# 8x8LED_Matrix_v1_0.net
KiCad netlist of a schematic drawn in EAGLE
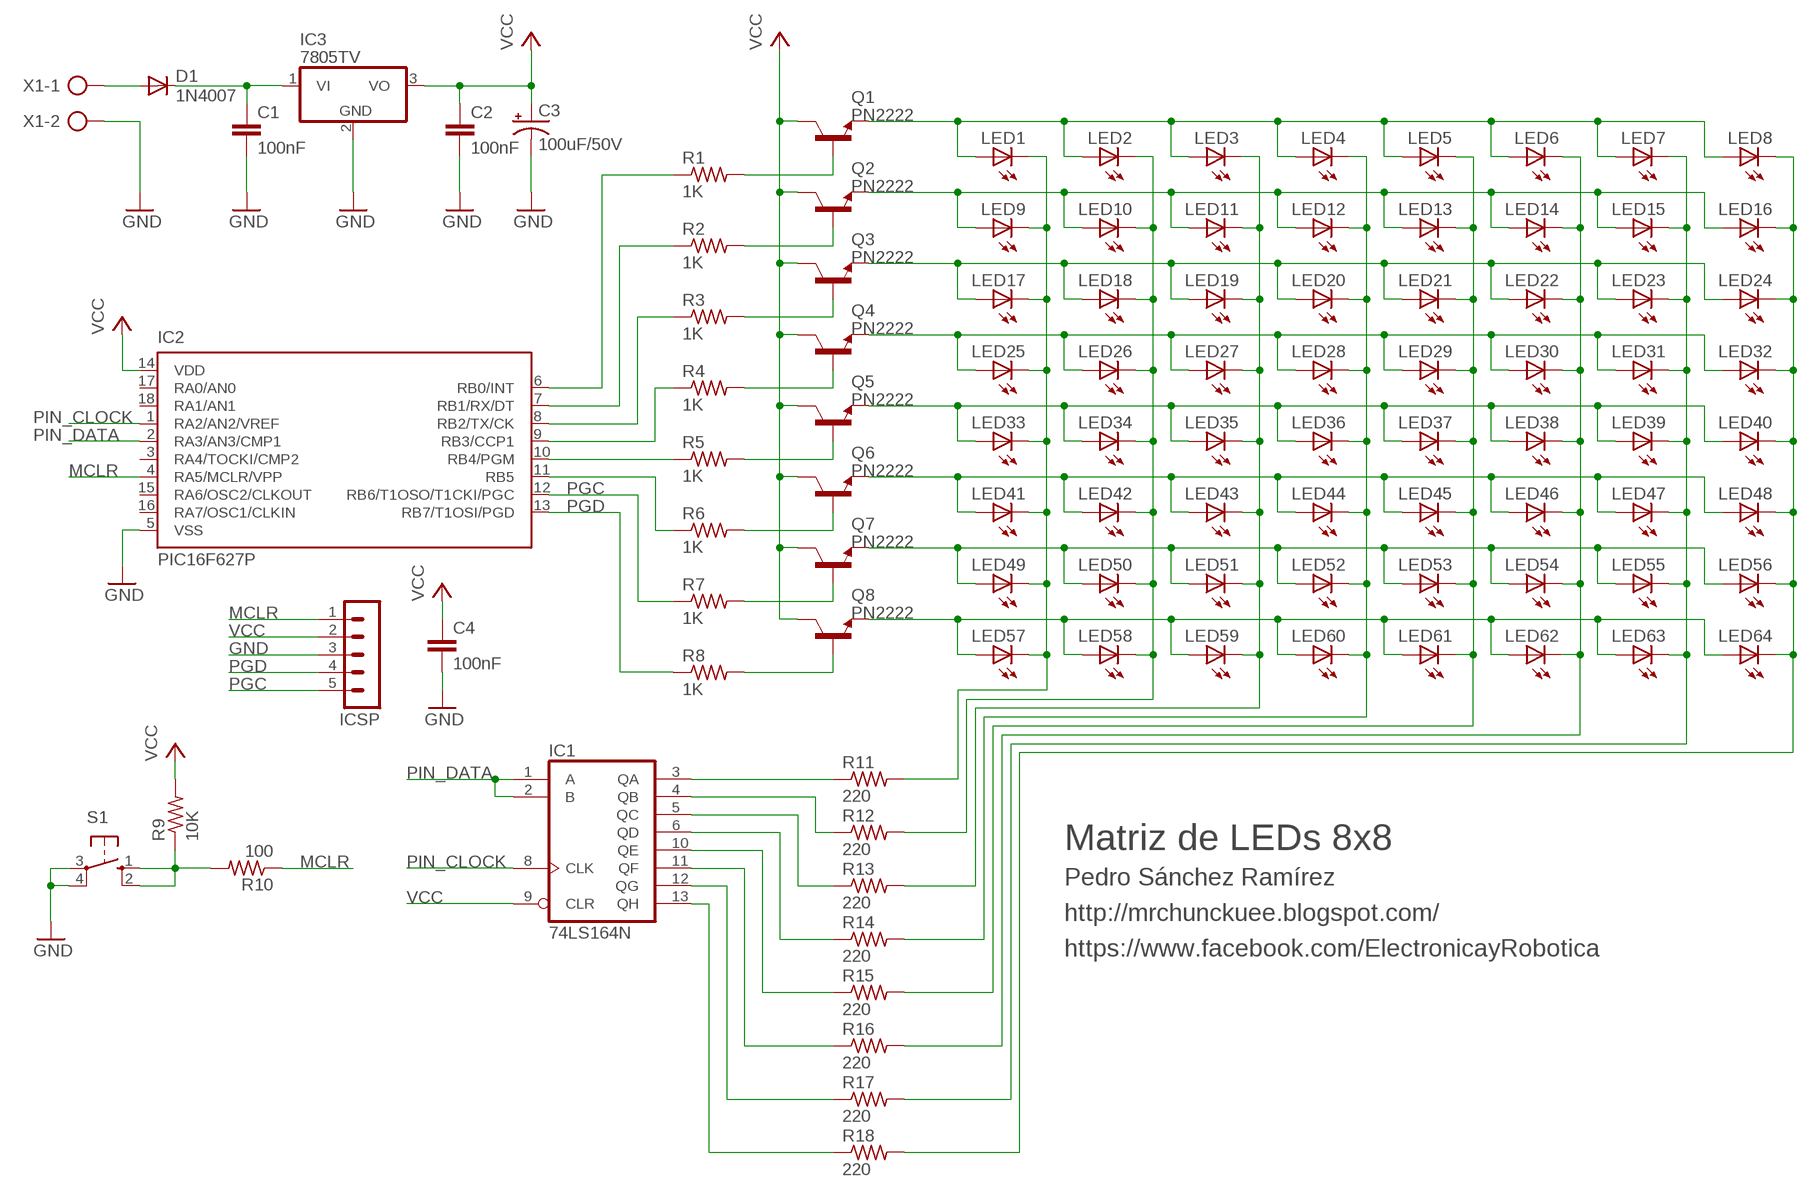
[diagram p0: schematic, sheet 1]

(export (version "E")
  (design (tool "Eeschema 10.0.6"))
  (components
    (comp (ref "C1")
      (value "100nF")
      (footprint "eagle-import:C050-024X044")
      (libsource (lib "eagle-import") (part "C-EU050-024X044"))
    )
    (comp (ref "C2")
      (value "100nF")
      (footprint "eagle-import:C050-024X044")
      (libsource (lib "eagle-import") (part "C-EU050-024X044"))
    )
    (comp (ref "C3")
      (value "100uF/50V")
      (footprint "eagle-import:E5-10,5")
      (libsource (lib "eagle-import") (part "CPOL-USE5-10.5"))
    )
    (comp (ref "C4")
      (value "100nF")
      (footprint "eagle-import:C050-024X044")
      (libsource (lib "eagle-import") (part "C-EU050-024X044"))
    )
    (comp (ref "D1")
      (value "1N4007")
      (footprint "eagle-import:DO41-10")
      (libsource (lib "eagle-import") (part "1N4004"))
    )
    (comp (ref "IC1")
      (value "74LS164N")
      (footprint "eagle-import:DIL14")
      (libsource (lib "eagle-import") (part "74164NLS"))
    )
    (comp (ref "IC2")
      (value "PIC16F627P")
      (footprint "eagle-import:DIL18")
      (fields (field (name "MF") "MICROCHIP") (field (name "MPN") "PIC16F627-04/P"))
      (libsource (lib "eagle-import") (part "PIC16F62P7"))
    )
    (comp (ref "IC3")
      (value "7805TV")
      (footprint "eagle-import:TO220V")
      (libsource (lib "eagle-import") (part "78TV05"))
    )
    (comp (ref "ICSP")
      (value "MA05-1")
      (footprint "eagle-import:MA05-1")
      (libsource (lib "eagle-import") (part "MA05-1"))
    )
    (comp (ref "LED1")
      (value "LED5MM")
      (footprint "eagle-import:LED5MM")
      (libsource (lib "eagle-import") (part "LED5MM"))
    )
    (comp (ref "LED2")
      (value "LED5MM")
      (footprint "eagle-import:LED5MM")
      (libsource (lib "eagle-import") (part "LED5MM"))
    )
    (comp (ref "LED3")
      (value "LED5MM")
      (footprint "eagle-import:LED5MM")
      (libsource (lib "eagle-import") (part "LED5MM"))
    )
    (comp (ref "LED4")
      (value "LED5MM")
      (footprint "eagle-import:LED5MM")
      (libsource (lib "eagle-import") (part "LED5MM"))
    )
    (comp (ref "LED5")
      (value "LED5MM")
      (footprint "eagle-import:LED5MM")
      (libsource (lib "eagle-import") (part "LED5MM"))
    )
    (comp (ref "LED6")
      (value "LED5MM")
      (footprint "eagle-import:LED5MM")
      (libsource (lib "eagle-import") (part "LED5MM"))
    )
    (comp (ref "LED7")
      (value "LED5MM")
      (footprint "eagle-import:LED5MM")
      (libsource (lib "eagle-import") (part "LED5MM"))
    )
    (comp (ref "LED8")
      (value "LED5MM")
      (footprint "eagle-import:LED5MM")
      (libsource (lib "eagle-import") (part "LED5MM"))
    )
    (comp (ref "LED9")
      (value "LED5MM")
      (footprint "eagle-import:LED5MM")
      (libsource (lib "eagle-import") (part "LED5MM"))
    )
    (comp (ref "LED10")
      (value "LED5MM")
      (footprint "eagle-import:LED5MM")
      (libsource (lib "eagle-import") (part "LED5MM"))
    )
    (comp (ref "LED11")
      (value "LED5MM")
      (footprint "eagle-import:LED5MM")
      (libsource (lib "eagle-import") (part "LED5MM"))
    )
    (comp (ref "LED12")
      (value "LED5MM")
      (footprint "eagle-import:LED5MM")
      (libsource (lib "eagle-import") (part "LED5MM"))
    )
    (comp (ref "LED13")
      (value "LED5MM")
      (footprint "eagle-import:LED5MM")
      (libsource (lib "eagle-import") (part "LED5MM"))
    )
    (comp (ref "LED14")
      (value "LED5MM")
      (footprint "eagle-import:LED5MM")
      (libsource (lib "eagle-import") (part "LED5MM"))
    )
    (comp (ref "LED15")
      (value "LED5MM")
      (footprint "eagle-import:LED5MM")
      (libsource (lib "eagle-import") (part "LED5MM"))
    )
    (comp (ref "LED16")
      (value "LED5MM")
      (footprint "eagle-import:LED5MM")
      (libsource (lib "eagle-import") (part "LED5MM"))
    )
    (comp (ref "LED17")
      (value "LED5MM")
      (footprint "eagle-import:LED5MM")
      (libsource (lib "eagle-import") (part "LED5MM"))
    )
    (comp (ref "LED18")
      (value "LED5MM")
      (footprint "eagle-import:LED5MM")
      (libsource (lib "eagle-import") (part "LED5MM"))
    )
    (comp (ref "LED19")
      (value "LED5MM")
      (footprint "eagle-import:LED5MM")
      (libsource (lib "eagle-import") (part "LED5MM"))
    )
    (comp (ref "LED20")
      (value "LED5MM")
      (footprint "eagle-import:LED5MM")
      (libsource (lib "eagle-import") (part "LED5MM"))
    )
    (comp (ref "LED21")
      (value "LED5MM")
      (footprint "eagle-import:LED5MM")
      (libsource (lib "eagle-import") (part "LED5MM"))
    )
    (comp (ref "LED22")
      (value "LED5MM")
      (footprint "eagle-import:LED5MM")
      (libsource (lib "eagle-import") (part "LED5MM"))
    )
    (comp (ref "LED23")
      (value "LED5MM")
      (footprint "eagle-import:LED5MM")
      (libsource (lib "eagle-import") (part "LED5MM"))
    )
    (comp (ref "LED24")
      (value "LED5MM")
      (footprint "eagle-import:LED5MM")
      (libsource (lib "eagle-import") (part "LED5MM"))
    )
    (comp (ref "LED25")
      (value "LED5MM")
      (footprint "eagle-import:LED5MM")
      (libsource (lib "eagle-import") (part "LED5MM"))
    )
    (comp (ref "LED26")
      (value "LED5MM")
      (footprint "eagle-import:LED5MM")
      (libsource (lib "eagle-import") (part "LED5MM"))
    )
    (comp (ref "LED27")
      (value "LED5MM")
      (footprint "eagle-import:LED5MM")
      (libsource (lib "eagle-import") (part "LED5MM"))
    )
    (comp (ref "LED28")
      (value "LED5MM")
      (footprint "eagle-import:LED5MM")
      (libsource (lib "eagle-import") (part "LED5MM"))
    )
    (comp (ref "LED29")
      (value "LED5MM")
      (footprint "eagle-import:LED5MM")
      (libsource (lib "eagle-import") (part "LED5MM"))
    )
    (comp (ref "LED30")
      (value "LED5MM")
      (footprint "eagle-import:LED5MM")
      (libsource (lib "eagle-import") (part "LED5MM"))
    )
    (comp (ref "LED31")
      (value "LED5MM")
      (footprint "eagle-import:LED5MM")
      (libsource (lib "eagle-import") (part "LED5MM"))
    )
    (comp (ref "LED32")
      (value "LED5MM")
      (footprint "eagle-import:LED5MM")
      (libsource (lib "eagle-import") (part "LED5MM"))
    )
    (comp (ref "LED33")
      (value "LED5MM")
      (footprint "eagle-import:LED5MM")
      (libsource (lib "eagle-import") (part "LED5MM"))
    )
    (comp (ref "LED34")
      (value "LED5MM")
      (footprint "eagle-import:LED5MM")
      (libsource (lib "eagle-import") (part "LED5MM"))
    )
    (comp (ref "LED35")
      (value "LED5MM")
      (footprint "eagle-import:LED5MM")
      (libsource (lib "eagle-import") (part "LED5MM"))
    )
    (comp (ref "LED36")
      (value "LED5MM")
      (footprint "eagle-import:LED5MM")
      (libsource (lib "eagle-import") (part "LED5MM"))
    )
    (comp (ref "LED37")
      (value "LED5MM")
      (footprint "eagle-import:LED5MM")
      (libsource (lib "eagle-import") (part "LED5MM"))
    )
    (comp (ref "LED38")
      (value "LED5MM")
      (footprint "eagle-import:LED5MM")
      (libsource (lib "eagle-import") (part "LED5MM"))
    )
    (comp (ref "LED39")
      (value "LED5MM")
      (footprint "eagle-import:LED5MM")
      (libsource (lib "eagle-import") (part "LED5MM"))
    )
    (comp (ref "LED40")
      (value "LED5MM")
      (footprint "eagle-import:LED5MM")
      (libsource (lib "eagle-import") (part "LED5MM"))
    )
    (comp (ref "LED41")
      (value "LED5MM")
      (footprint "eagle-import:LED5MM")
      (libsource (lib "eagle-import") (part "LED5MM"))
    )
    (comp (ref "LED42")
      (value "LED5MM")
      (footprint "eagle-import:LED5MM")
      (libsource (lib "eagle-import") (part "LED5MM"))
    )
    (comp (ref "LED43")
      (value "LED5MM")
      (footprint "eagle-import:LED5MM")
      (libsource (lib "eagle-import") (part "LED5MM"))
    )
    (comp (ref "LED44")
      (value "LED5MM")
      (footprint "eagle-import:LED5MM")
      (libsource (lib "eagle-import") (part "LED5MM"))
    )
    (comp (ref "LED45")
      (value "LED5MM")
      (footprint "eagle-import:LED5MM")
      (libsource (lib "eagle-import") (part "LED5MM"))
    )
    (comp (ref "LED46")
      (value "LED5MM")
      (footprint "eagle-import:LED5MM")
      (libsource (lib "eagle-import") (part "LED5MM"))
    )
    (comp (ref "LED47")
      (value "LED5MM")
      (footprint "eagle-import:LED5MM")
      (libsource (lib "eagle-import") (part "LED5MM"))
    )
    (comp (ref "LED48")
      (value "LED5MM")
      (footprint "eagle-import:LED5MM")
      (libsource (lib "eagle-import") (part "LED5MM"))
    )
    (comp (ref "LED49")
      (value "LED5MM")
      (footprint "eagle-import:LED5MM")
      (libsource (lib "eagle-import") (part "LED5MM"))
    )
    (comp (ref "LED50")
      (value "LED5MM")
      (footprint "eagle-import:LED5MM")
      (libsource (lib "eagle-import") (part "LED5MM"))
    )
    (comp (ref "LED51")
      (value "LED5MM")
      (footprint "eagle-import:LED5MM")
      (libsource (lib "eagle-import") (part "LED5MM"))
    )
    (comp (ref "LED52")
      (value "LED5MM")
      (footprint "eagle-import:LED5MM")
      (libsource (lib "eagle-import") (part "LED5MM"))
    )
    (comp (ref "LED53")
      (value "LED5MM")
      (footprint "eagle-import:LED5MM")
      (libsource (lib "eagle-import") (part "LED5MM"))
    )
    (comp (ref "LED54")
      (value "LED5MM")
      (footprint "eagle-import:LED5MM")
      (libsource (lib "eagle-import") (part "LED5MM"))
    )
    (comp (ref "LED55")
      (value "LED5MM")
      (footprint "eagle-import:LED5MM")
      (libsource (lib "eagle-import") (part "LED5MM"))
    )
    (comp (ref "LED56")
      (value "LED5MM")
      (footprint "eagle-import:LED5MM")
      (libsource (lib "eagle-import") (part "LED5MM"))
    )
    (comp (ref "LED57")
      (value "LED5MM")
      (footprint "eagle-import:LED5MM")
      (libsource (lib "eagle-import") (part "LED5MM"))
    )
    (comp (ref "LED58")
      (value "LED5MM")
      (footprint "eagle-import:LED5MM")
      (libsource (lib "eagle-import") (part "LED5MM"))
    )
    (comp (ref "LED59")
      (value "LED5MM")
      (footprint "eagle-import:LED5MM")
      (libsource (lib "eagle-import") (part "LED5MM"))
    )
    (comp (ref "LED60")
      (value "LED5MM")
      (footprint "eagle-import:LED5MM")
      (libsource (lib "eagle-import") (part "LED5MM"))
    )
    (comp (ref "LED61")
      (value "LED5MM")
      (footprint "eagle-import:LED5MM")
      (libsource (lib "eagle-import") (part "LED5MM"))
    )
    (comp (ref "LED62")
      (value "LED5MM")
      (footprint "eagle-import:LED5MM")
      (libsource (lib "eagle-import") (part "LED5MM"))
    )
    (comp (ref "LED63")
      (value "LED5MM")
      (footprint "eagle-import:LED5MM")
      (libsource (lib "eagle-import") (part "LED5MM"))
    )
    (comp (ref "LED64")
      (value "LED5MM")
      (footprint "eagle-import:LED5MM")
      (libsource (lib "eagle-import") (part "LED5MM"))
    )
    (comp (ref "Q1")
      (value "PN2222")
      (footprint "eagle-import:TO92-EBC")
      (libsource (lib "eagle-import") (part "-NPN-TO92-EBC2N4124"))
    )
    (comp (ref "Q2")
      (value "PN2222")
      (footprint "eagle-import:TO92-EBC")
      (libsource (lib "eagle-import") (part "-NPN-TO92-EBC2N4124"))
    )
    (comp (ref "Q3")
      (value "PN2222")
      (footprint "eagle-import:TO92-EBC")
      (libsource (lib "eagle-import") (part "-NPN-TO92-EBC2N4124"))
    )
    (comp (ref "Q4")
      (value "PN2222")
      (footprint "eagle-import:TO92-EBC")
      (libsource (lib "eagle-import") (part "-NPN-TO92-EBC2N4124"))
    )
    (comp (ref "Q5")
      (value "PN2222")
      (footprint "eagle-import:TO92-EBC")
      (libsource (lib "eagle-import") (part "-NPN-TO92-EBC2N4124"))
    )
    (comp (ref "Q6")
      (value "PN2222")
      (footprint "eagle-import:TO92-EBC")
      (libsource (lib "eagle-import") (part "-NPN-TO92-EBC2N4124"))
    )
    (comp (ref "Q7")
      (value "PN2222")
      (footprint "eagle-import:TO92-EBC")
      (libsource (lib "eagle-import") (part "-NPN-TO92-EBC2N4124"))
    )
    (comp (ref "Q8")
      (value "PN2222")
      (footprint "eagle-import:TO92-EBC")
      (libsource (lib "eagle-import") (part "-NPN-TO92-EBC2N4124"))
    )
    (comp (ref "R1")
      (value "1K")
      (footprint "eagle-import:0204_7")
      (libsource (lib "eagle-import") (part "R-US_0204/7"))
    )
    (comp (ref "R2")
      (value "1K")
      (footprint "eagle-import:0204_7")
      (libsource (lib "eagle-import") (part "R-US_0204/7"))
    )
    (comp (ref "R3")
      (value "1K")
      (footprint "eagle-import:0204_7")
      (libsource (lib "eagle-import") (part "R-US_0204/7"))
    )
    (comp (ref "R4")
      (value "1K")
      (footprint "eagle-import:0204_7")
      (libsource (lib "eagle-import") (part "R-US_0204/7"))
    )
    (comp (ref "R5")
      (value "1K")
      (footprint "eagle-import:0204_7")
      (libsource (lib "eagle-import") (part "R-US_0204/7"))
    )
    (comp (ref "R6")
      (value "1K")
      (footprint "eagle-import:0204_7")
      (libsource (lib "eagle-import") (part "R-US_0204/7"))
    )
    (comp (ref "R7")
      (value "1K")
      (footprint "eagle-import:0204_7")
      (libsource (lib "eagle-import") (part "R-US_0204/7"))
    )
    (comp (ref "R8")
      (value "1K")
      (footprint "eagle-import:0204_7")
      (libsource (lib "eagle-import") (part "R-US_0204/7"))
    )
    (comp (ref "R9")
      (value "10K")
      (footprint "eagle-import:0204_7")
      (libsource (lib "eagle-import") (part "R-US_0204/7"))
    )
    (comp (ref "R10")
      (value "100")
      (footprint "eagle-import:0204_7")
      (libsource (lib "eagle-import") (part "R-US_0204/7"))
    )
    (comp (ref "R11")
      (value "220")
      (footprint "eagle-import:0204_7")
      (libsource (lib "eagle-import") (part "R-US_0204/7"))
    )
    (comp (ref "R12")
      (value "220")
      (footprint "eagle-import:0204_7")
      (libsource (lib "eagle-import") (part "R-US_0204/7"))
    )
    (comp (ref "R13")
      (value "220")
      (footprint "eagle-import:0204_7")
      (libsource (lib "eagle-import") (part "R-US_0204/7"))
    )
    (comp (ref "R14")
      (value "220")
      (footprint "eagle-import:0204_7")
      (libsource (lib "eagle-import") (part "R-US_0204/7"))
    )
    (comp (ref "R15")
      (value "220")
      (footprint "eagle-import:0204_7")
      (libsource (lib "eagle-import") (part "R-US_0204/7"))
    )
    (comp (ref "R16")
      (value "220")
      (footprint "eagle-import:0204_7")
      (libsource (lib "eagle-import") (part "R-US_0204/7"))
    )
    (comp (ref "R17")
      (value "220")
      (footprint "eagle-import:0204_7")
      (libsource (lib "eagle-import") (part "R-US_0204/7"))
    )
    (comp (ref "R18")
      (value "220")
      (footprint "eagle-import:0204_7")
      (libsource (lib "eagle-import") (part "R-US_0204/7"))
    )
    (comp (ref "S1")
      (value "10-XX")
      (footprint "eagle-import:B3F-10XX")
      (fields (field (name "MPN") "B3F-1000"))
      (libsource (lib "eagle-import") (part "10-XX"))
    )
    (comp (ref "X1")
      (value "AK500/2-H")
      (footprint "eagle-import:AK500_2-H")
      (libsource (lib "eagle-import") (part "AK500/2-H"))
    )
  )
  (nets
    (net (code "1") (name "/MCLR") (class "Default")
      (node (ref "IC2") (pin "4") (pinfunction "RA5/MCLR/VPP_4") (pintype "bidirectional"))
      (node (ref "ICSP") (pin "1") (pinfunction "1_1") (pintype "passive"))
      (node (ref "R10") (pin "1") (pinfunction "1_1") (pintype "passive"))
    )
    (net (code "2") (name "/PGC") (class "Default")
      (node (ref "IC2") (pin "12") (pinfunction "RB6/T1OSO/T1CKI/PGC_12") (pintype "bidirectional"))
      (node (ref "ICSP") (pin "5") (pinfunction "5_5") (pintype "passive"))
      (node (ref "R7") (pin "1") (pinfunction "1_1") (pintype "passive"))
    )
    (net (code "3") (name "/PGD") (class "Default")
      (node (ref "IC2") (pin "13") (pinfunction "RB7/T1OSI/PGD_13") (pintype "bidirectional"))
      (node (ref "ICSP") (pin "4") (pinfunction "4_4") (pintype "passive"))
      (node (ref "R8") (pin "1") (pinfunction "1_1") (pintype "passive"))
    )
    (net (code "4") (name "/PIN_CLOCK") (class "Default")
      (node (ref "IC1") (pin "8") (pinfunction "CLK_8") (pintype "input"))
      (node (ref "IC2") (pin "1") (pinfunction "RA2/AN2/VREF_1") (pintype "bidirectional"))
    )
    (net (code "5") (name "/PIN_DATA") (class "Default")
      (node (ref "IC1") (pin "1") (pinfunction "A_1") (pintype "input"))
      (node (ref "IC1") (pin "2") (pinfunction "B_2") (pintype "input"))
      (node (ref "IC2") (pin "2") (pinfunction "RA3/AN3/CMP1_2") (pintype "bidirectional"))
    )
    (net (code "6") (name "GND") (class "Default")
      (node (ref "C1") (pin "2") (pinfunction "2_2") (pintype "passive"))
      (node (ref "C2") (pin "2") (pinfunction "2_2") (pintype "passive"))
      (node (ref "C3") (pin "-") (pinfunction "-_-") (pintype "passive"))
      (node (ref "C4") (pin "2") (pinfunction "2_2") (pintype "passive"))
      (node (ref "IC2") (pin "5") (pinfunction "VSS_5") (pintype "power_in"))
      (node (ref "IC3") (pin "2") (pinfunction "GND_2") (pintype "passive"))
      (node (ref "ICSP") (pin "3") (pinfunction "3_3") (pintype "passive"))
      (node (ref "S1") (pin "3") (pinfunction "P_3") (pintype "passive"))
      (node (ref "S1") (pin "4") (pinfunction "P1_4") (pintype "passive"))
      (node (ref "X1") (pin "2") (pinfunction "KL_2") (pintype "passive"))
    )
    (net (code "7") (name "Net-(IC1A-QA)") (class "Default")
      (node (ref "IC1") (pin "3") (pinfunction "QA_3") (pintype "output"))
      (node (ref "R11") (pin "1") (pinfunction "1_1") (pintype "passive"))
    )
    (net (code "8") (name "Net-(IC1A-QB)") (class "Default")
      (node (ref "IC1") (pin "4") (pinfunction "QB_4") (pintype "output"))
      (node (ref "R12") (pin "1") (pinfunction "1_1") (pintype "passive"))
    )
    (net (code "9") (name "Net-(IC1A-QC)") (class "Default")
      (node (ref "IC1") (pin "5") (pinfunction "QC_5") (pintype "output"))
      (node (ref "R13") (pin "1") (pinfunction "1_1") (pintype "passive"))
    )
    (net (code "10") (name "Net-(IC1A-QD)") (class "Default")
      (node (ref "IC1") (pin "6") (pinfunction "QD_6") (pintype "output"))
      (node (ref "R14") (pin "1") (pinfunction "1_1") (pintype "passive"))
    )
    (net (code "11") (name "Net-(IC1A-QE)") (class "Default")
      (node (ref "IC1") (pin "10") (pinfunction "QE_10") (pintype "output"))
      (node (ref "R15") (pin "1") (pinfunction "1_1") (pintype "passive"))
    )
    (net (code "12") (name "Net-(IC1A-QF)") (class "Default")
      (node (ref "IC1") (pin "11") (pinfunction "QF_11") (pintype "output"))
      (node (ref "R16") (pin "1") (pinfunction "1_1") (pintype "passive"))
    )
    (net (code "13") (name "Net-(IC1A-QG)") (class "Default")
      (node (ref "IC1") (pin "12") (pinfunction "QG_12") (pintype "output"))
      (node (ref "R17") (pin "1") (pinfunction "1_1") (pintype "passive"))
    )
    (net (code "14") (name "Net-(IC1A-QH)") (class "Default")
      (node (ref "IC1") (pin "13") (pinfunction "QH_13") (pintype "output"))
      (node (ref "R18") (pin "1") (pinfunction "1_1") (pintype "passive"))
    )
    (net (code "15") (name "Net-(IC2-RB0{slash}INT)") (class "Default")
      (node (ref "IC2") (pin "6") (pinfunction "RB0/INT_6") (pintype "bidirectional"))
      (node (ref "R1") (pin "1") (pinfunction "1_1") (pintype "passive"))
    )
    (net (code "16") (name "Net-(IC2-RB1{slash}RX{slash}DT)") (class "Default")
      (node (ref "IC2") (pin "7") (pinfunction "RB1/RX/DT_7") (pintype "bidirectional"))
      (node (ref "R2") (pin "1") (pinfunction "1_1") (pintype "passive"))
    )
    (net (code "17") (name "Net-(IC2-RB2{slash}TX{slash}CK)") (class "Default")
      (node (ref "IC2") (pin "8") (pinfunction "RB2/TX/CK_8") (pintype "bidirectional"))
      (node (ref "R3") (pin "1") (pinfunction "1_1") (pintype "passive"))
    )
    (net (code "18") (name "Net-(IC2-RB3{slash}CCP1)") (class "Default")
      (node (ref "IC2") (pin "9") (pinfunction "RB3/CCP1_9") (pintype "bidirectional"))
      (node (ref "R4") (pin "1") (pinfunction "1_1") (pintype "passive"))
    )
    (net (code "19") (name "Net-(IC2-RB4{slash}PGM)") (class "Default")
      (node (ref "IC2") (pin "10") (pinfunction "RB4/PGM_10") (pintype "bidirectional"))
      (node (ref "R5") (pin "1") (pinfunction "1_1") (pintype "passive"))
    )
    (net (code "20") (name "Net-(IC2-RB5)") (class "Default")
      (node (ref "IC2") (pin "11") (pinfunction "RB5_11") (pintype "bidirectional"))
      (node (ref "R6") (pin "1") (pinfunction "1_1") (pintype "passive"))
    )
    (net (code "21") (name "Net-(IC3-VI)") (class "Default")
      (node (ref "C1") (pin "1") (pinfunction "1_1") (pintype "passive"))
      (node (ref "D1") (pin "C") (pinfunction "C_C") (pintype "passive"))
      (node (ref "IC3") (pin "1") (pinfunction "VI_1") (pintype "input"))
    )
    (net (code "22") (name "Net-(LED1-C)") (class "Default")
      (node (ref "LED1") (pin "K") (pinfunction "C_K") (pintype "passive"))
      (node (ref "LED17") (pin "K") (pinfunction "C_K") (pintype "passive"))
      (node (ref "LED25") (pin "K") (pinfunction "C_K") (pintype "passive"))
      (node (ref "LED33") (pin "K") (pinfunction "C_K") (pintype "passive"))
      (node (ref "LED41") (pin "K") (pinfunction "C_K") (pintype "passive"))
      (node (ref "LED49") (pin "K") (pinfunction "C_K") (pintype "passive"))
      (node (ref "LED57") (pin "K") (pinfunction "C_K") (pintype "passive"))
      (node (ref "LED9") (pin "K") (pinfunction "C_K") (pintype "passive"))
      (node (ref "R11") (pin "2") (pinfunction "2_2") (pintype "passive"))
    )
    (net (code "23") (name "Net-(LED1-PadA)") (class "Default")
      (node (ref "LED1") (pin "A") (pinfunction "A_A") (pintype "passive"))
      (node (ref "LED2") (pin "A") (pinfunction "A_A") (pintype "passive"))
      (node (ref "LED3") (pin "A") (pinfunction "A_A") (pintype "passive"))
      (node (ref "LED4") (pin "A") (pinfunction "A_A") (pintype "passive"))
      (node (ref "LED5") (pin "A") (pinfunction "A_A") (pintype "passive"))
      (node (ref "LED6") (pin "A") (pinfunction "A_A") (pintype "passive"))
      (node (ref "LED7") (pin "A") (pinfunction "A_A") (pintype "passive"))
      (node (ref "LED8") (pin "A") (pinfunction "A_A") (pintype "passive"))
      (node (ref "Q1") (pin "E") (pinfunction "E_E") (pintype "passive"))
    )
    (net (code "24") (name "Net-(LED10-C)") (class "Default")
      (node (ref "LED10") (pin "K") (pinfunction "C_K") (pintype "passive"))
      (node (ref "LED18") (pin "K") (pinfunction "C_K") (pintype "passive"))
      (node (ref "LED2") (pin "K") (pinfunction "C_K") (pintype "passive"))
      (node (ref "LED26") (pin "K") (pinfunction "C_K") (pintype "passive"))
      (node (ref "LED34") (pin "K") (pinfunction "C_K") (pintype "passive"))
      (node (ref "LED42") (pin "K") (pinfunction "C_K") (pintype "passive"))
      (node (ref "LED50") (pin "K") (pinfunction "C_K") (pintype "passive"))
      (node (ref "LED58") (pin "K") (pinfunction "C_K") (pintype "passive"))
      (node (ref "R12") (pin "2") (pinfunction "2_2") (pintype "passive"))
    )
    (net (code "25") (name "Net-(LED10-PadA)") (class "Default")
      (node (ref "LED10") (pin "A") (pinfunction "A_A") (pintype "passive"))
      (node (ref "LED11") (pin "A") (pinfunction "A_A") (pintype "passive"))
      (node (ref "LED12") (pin "A") (pinfunction "A_A") (pintype "passive"))
      (node (ref "LED13") (pin "A") (pinfunction "A_A") (pintype "passive"))
      (node (ref "LED14") (pin "A") (pinfunction "A_A") (pintype "passive"))
      (node (ref "LED15") (pin "A") (pinfunction "A_A") (pintype "passive"))
      (node (ref "LED16") (pin "A") (pinfunction "A_A") (pintype "passive"))
      (node (ref "LED9") (pin "A") (pinfunction "A_A") (pintype "passive"))
      (node (ref "Q2") (pin "E") (pinfunction "E_E") (pintype "passive"))
    )
    (net (code "26") (name "Net-(LED11-C)") (class "Default")
      (node (ref "LED11") (pin "K") (pinfunction "C_K") (pintype "passive"))
      (node (ref "LED19") (pin "K") (pinfunction "C_K") (pintype "passive"))
      (node (ref "LED27") (pin "K") (pinfunction "C_K") (pintype "passive"))
      (node (ref "LED3") (pin "K") (pinfunction "C_K") (pintype "passive"))
      (node (ref "LED35") (pin "K") (pinfunction "C_K") (pintype "passive"))
      (node (ref "LED43") (pin "K") (pinfunction "C_K") (pintype "passive"))
      (node (ref "LED51") (pin "K") (pinfunction "C_K") (pintype "passive"))
      (node (ref "LED59") (pin "K") (pinfunction "C_K") (pintype "passive"))
      (node (ref "R13") (pin "2") (pinfunction "2_2") (pintype "passive"))
    )
    (net (code "27") (name "Net-(LED12-C)") (class "Default")
      (node (ref "LED12") (pin "K") (pinfunction "C_K") (pintype "passive"))
      (node (ref "LED20") (pin "K") (pinfunction "C_K") (pintype "passive"))
      (node (ref "LED28") (pin "K") (pinfunction "C_K") (pintype "passive"))
      (node (ref "LED36") (pin "K") (pinfunction "C_K") (pintype "passive"))
      (node (ref "LED4") (pin "K") (pinfunction "C_K") (pintype "passive"))
      (node (ref "LED44") (pin "K") (pinfunction "C_K") (pintype "passive"))
      (node (ref "LED52") (pin "K") (pinfunction "C_K") (pintype "passive"))
      (node (ref "LED60") (pin "K") (pinfunction "C_K") (pintype "passive"))
      (node (ref "R14") (pin "2") (pinfunction "2_2") (pintype "passive"))
    )
    (net (code "28") (name "Net-(LED13-C)") (class "Default")
      (node (ref "LED13") (pin "K") (pinfunction "C_K") (pintype "passive"))
      (node (ref "LED21") (pin "K") (pinfunction "C_K") (pintype "passive"))
      (node (ref "LED29") (pin "K") (pinfunction "C_K") (pintype "passive"))
      (node (ref "LED37") (pin "K") (pinfunction "C_K") (pintype "passive"))
      (node (ref "LED45") (pin "K") (pinfunction "C_K") (pintype "passive"))
      (node (ref "LED5") (pin "K") (pinfunction "C_K") (pintype "passive"))
      (node (ref "LED53") (pin "K") (pinfunction "C_K") (pintype "passive"))
      (node (ref "LED61") (pin "K") (pinfunction "C_K") (pintype "passive"))
      (node (ref "R15") (pin "2") (pinfunction "2_2") (pintype "passive"))
    )
    (net (code "29") (name "Net-(LED14-C)") (class "Default")
      (node (ref "LED14") (pin "K") (pinfunction "C_K") (pintype "passive"))
      (node (ref "LED22") (pin "K") (pinfunction "C_K") (pintype "passive"))
      (node (ref "LED30") (pin "K") (pinfunction "C_K") (pintype "passive"))
      (node (ref "LED38") (pin "K") (pinfunction "C_K") (pintype "passive"))
      (node (ref "LED46") (pin "K") (pinfunction "C_K") (pintype "passive"))
      (node (ref "LED54") (pin "K") (pinfunction "C_K") (pintype "passive"))
      (node (ref "LED6") (pin "K") (pinfunction "C_K") (pintype "passive"))
      (node (ref "LED62") (pin "K") (pinfunction "C_K") (pintype "passive"))
      (node (ref "R16") (pin "2") (pinfunction "2_2") (pintype "passive"))
    )
    (net (code "30") (name "Net-(LED15-C)") (class "Default")
      (node (ref "LED15") (pin "K") (pinfunction "C_K") (pintype "passive"))
      (node (ref "LED23") (pin "K") (pinfunction "C_K") (pintype "passive"))
      (node (ref "LED31") (pin "K") (pinfunction "C_K") (pintype "passive"))
      (node (ref "LED39") (pin "K") (pinfunction "C_K") (pintype "passive"))
      (node (ref "LED47") (pin "K") (pinfunction "C_K") (pintype "passive"))
      (node (ref "LED55") (pin "K") (pinfunction "C_K") (pintype "passive"))
      (node (ref "LED63") (pin "K") (pinfunction "C_K") (pintype "passive"))
      (node (ref "LED7") (pin "K") (pinfunction "C_K") (pintype "passive"))
      (node (ref "R17") (pin "2") (pinfunction "2_2") (pintype "passive"))
    )
    (net (code "31") (name "Net-(LED16-C)") (class "Default")
      (node (ref "LED16") (pin "K") (pinfunction "C_K") (pintype "passive"))
      (node (ref "LED24") (pin "K") (pinfunction "C_K") (pintype "passive"))
      (node (ref "LED32") (pin "K") (pinfunction "C_K") (pintype "passive"))
      (node (ref "LED40") (pin "K") (pinfunction "C_K") (pintype "passive"))
      (node (ref "LED48") (pin "K") (pinfunction "C_K") (pintype "passive"))
      (node (ref "LED56") (pin "K") (pinfunction "C_K") (pintype "passive"))
      (node (ref "LED64") (pin "K") (pinfunction "C_K") (pintype "passive"))
      (node (ref "LED8") (pin "K") (pinfunction "C_K") (pintype "passive"))
      (node (ref "R18") (pin "2") (pinfunction "2_2") (pintype "passive"))
    )
    (net (code "32") (name "Net-(LED17-PadA)") (class "Default")
      (node (ref "LED17") (pin "A") (pinfunction "A_A") (pintype "passive"))
      (node (ref "LED18") (pin "A") (pinfunction "A_A") (pintype "passive"))
      (node (ref "LED19") (pin "A") (pinfunction "A_A") (pintype "passive"))
      (node (ref "LED20") (pin "A") (pinfunction "A_A") (pintype "passive"))
      (node (ref "LED21") (pin "A") (pinfunction "A_A") (pintype "passive"))
      (node (ref "LED22") (pin "A") (pinfunction "A_A") (pintype "passive"))
      (node (ref "LED23") (pin "A") (pinfunction "A_A") (pintype "passive"))
      (node (ref "LED24") (pin "A") (pinfunction "A_A") (pintype "passive"))
      (node (ref "Q3") (pin "E") (pinfunction "E_E") (pintype "passive"))
    )
    (net (code "33") (name "Net-(LED25-PadA)") (class "Default")
      (node (ref "LED25") (pin "A") (pinfunction "A_A") (pintype "passive"))
      (node (ref "LED26") (pin "A") (pinfunction "A_A") (pintype "passive"))
      (node (ref "LED27") (pin "A") (pinfunction "A_A") (pintype "passive"))
      (node (ref "LED28") (pin "A") (pinfunction "A_A") (pintype "passive"))
      (node (ref "LED29") (pin "A") (pinfunction "A_A") (pintype "passive"))
      (node (ref "LED30") (pin "A") (pinfunction "A_A") (pintype "passive"))
      (node (ref "LED31") (pin "A") (pinfunction "A_A") (pintype "passive"))
      (node (ref "LED32") (pin "A") (pinfunction "A_A") (pintype "passive"))
      (node (ref "Q4") (pin "E") (pinfunction "E_E") (pintype "passive"))
    )
    (net (code "34") (name "Net-(LED33-PadA)") (class "Default")
      (node (ref "LED33") (pin "A") (pinfunction "A_A") (pintype "passive"))
      (node (ref "LED34") (pin "A") (pinfunction "A_A") (pintype "passive"))
      (node (ref "LED35") (pin "A") (pinfunction "A_A") (pintype "passive"))
      (node (ref "LED36") (pin "A") (pinfunction "A_A") (pintype "passive"))
      (node (ref "LED37") (pin "A") (pinfunction "A_A") (pintype "passive"))
      (node (ref "LED38") (pin "A") (pinfunction "A_A") (pintype "passive"))
      (node (ref "LED39") (pin "A") (pinfunction "A_A") (pintype "passive"))
      (node (ref "LED40") (pin "A") (pinfunction "A_A") (pintype "passive"))
      (node (ref "Q5") (pin "E") (pinfunction "E_E") (pintype "passive"))
    )
    (net (code "35") (name "Net-(LED41-PadA)") (class "Default")
      (node (ref "LED41") (pin "A") (pinfunction "A_A") (pintype "passive"))
      (node (ref "LED42") (pin "A") (pinfunction "A_A") (pintype "passive"))
      (node (ref "LED43") (pin "A") (pinfunction "A_A") (pintype "passive"))
      (node (ref "LED44") (pin "A") (pinfunction "A_A") (pintype "passive"))
      (node (ref "LED45") (pin "A") (pinfunction "A_A") (pintype "passive"))
      (node (ref "LED46") (pin "A") (pinfunction "A_A") (pintype "passive"))
      (node (ref "LED47") (pin "A") (pinfunction "A_A") (pintype "passive"))
      (node (ref "LED48") (pin "A") (pinfunction "A_A") (pintype "passive"))
      (node (ref "Q6") (pin "E") (pinfunction "E_E") (pintype "passive"))
    )
    (net (code "36") (name "Net-(LED49-PadA)") (class "Default")
      (node (ref "LED49") (pin "A") (pinfunction "A_A") (pintype "passive"))
      (node (ref "LED50") (pin "A") (pinfunction "A_A") (pintype "passive"))
      (node (ref "LED51") (pin "A") (pinfunction "A_A") (pintype "passive"))
      (node (ref "LED52") (pin "A") (pinfunction "A_A") (pintype "passive"))
      (node (ref "LED53") (pin "A") (pinfunction "A_A") (pintype "passive"))
      (node (ref "LED54") (pin "A") (pinfunction "A_A") (pintype "passive"))
      (node (ref "LED55") (pin "A") (pinfunction "A_A") (pintype "passive"))
      (node (ref "LED56") (pin "A") (pinfunction "A_A") (pintype "passive"))
      (node (ref "Q7") (pin "E") (pinfunction "E_E") (pintype "passive"))
    )
    (net (code "37") (name "Net-(LED57-PadA)") (class "Default")
      (node (ref "LED57") (pin "A") (pinfunction "A_A") (pintype "passive"))
      (node (ref "LED58") (pin "A") (pinfunction "A_A") (pintype "passive"))
      (node (ref "LED59") (pin "A") (pinfunction "A_A") (pintype "passive"))
      (node (ref "LED60") (pin "A") (pinfunction "A_A") (pintype "passive"))
      (node (ref "LED61") (pin "A") (pinfunction "A_A") (pintype "passive"))
      (node (ref "LED62") (pin "A") (pinfunction "A_A") (pintype "passive"))
      (node (ref "LED63") (pin "A") (pinfunction "A_A") (pintype "passive"))
      (node (ref "LED64") (pin "A") (pinfunction "A_A") (pintype "passive"))
      (node (ref "Q8") (pin "E") (pinfunction "E_E") (pintype "passive"))
    )
    (net (code "38") (name "Net-(Q1-PadB)") (class "Default")
      (node (ref "Q1") (pin "B") (pinfunction "B_B") (pintype "passive"))
      (node (ref "R1") (pin "2") (pinfunction "2_2") (pintype "passive"))
    )
    (net (code "39") (name "Net-(Q2-PadB)") (class "Default")
      (node (ref "Q2") (pin "B") (pinfunction "B_B") (pintype "passive"))
      (node (ref "R2") (pin "2") (pinfunction "2_2") (pintype "passive"))
    )
    (net (code "40") (name "Net-(Q3-PadB)") (class "Default")
      (node (ref "Q3") (pin "B") (pinfunction "B_B") (pintype "passive"))
      (node (ref "R3") (pin "2") (pinfunction "2_2") (pintype "passive"))
    )
    (net (code "41") (name "Net-(Q4-PadB)") (class "Default")
      (node (ref "Q4") (pin "B") (pinfunction "B_B") (pintype "passive"))
      (node (ref "R4") (pin "2") (pinfunction "2_2") (pintype "passive"))
    )
    (net (code "42") (name "Net-(Q5-PadB)") (class "Default")
      (node (ref "Q5") (pin "B") (pinfunction "B_B") (pintype "passive"))
      (node (ref "R5") (pin "2") (pinfunction "2_2") (pintype "passive"))
    )
    (net (code "43") (name "Net-(Q6-PadB)") (class "Default")
      (node (ref "Q6") (pin "B") (pinfunction "B_B") (pintype "passive"))
      (node (ref "R6") (pin "2") (pinfunction "2_2") (pintype "passive"))
    )
    (net (code "44") (name "Net-(Q7-PadB)") (class "Default")
      (node (ref "Q7") (pin "B") (pinfunction "B_B") (pintype "passive"))
      (node (ref "R7") (pin "2") (pinfunction "2_2") (pintype "passive"))
    )
    (net (code "45") (name "Net-(Q8-PadB)") (class "Default")
      (node (ref "Q8") (pin "B") (pinfunction "B_B") (pintype "passive"))
      (node (ref "R8") (pin "2") (pinfunction "2_2") (pintype "passive"))
    )
    (net (code "46") (name "Net-(S1-S)") (class "Default")
      (node (ref "R10") (pin "2") (pinfunction "2_2") (pintype "passive"))
      (node (ref "R9") (pin "1") (pinfunction "1_1") (pintype "passive"))
      (node (ref "S1") (pin "1") (pinfunction "S_1") (pintype "passive"))
      (node (ref "S1") (pin "2") (pinfunction "S1_2") (pintype "passive"))
    )
    (net (code "47") (name "Net-(X1A-KL)") (class "Default")
      (node (ref "D1") (pin "A") (pinfunction "A_A") (pintype "passive"))
      (node (ref "X1") (pin "1") (pinfunction "KL_1") (pintype "passive"))
    )
    (net (code "48") (name "VCC") (class "Default")
      (node (ref "C2") (pin "1") (pinfunction "1_1") (pintype "passive"))
      (node (ref "C3") (pin "+") (pinfunction "+_+") (pintype "passive"))
      (node (ref "C4") (pin "1") (pinfunction "1_1") (pintype "passive"))
      (node (ref "IC1") (pin "9") (pinfunction "CLR_9") (pintype "input"))
      (node (ref "IC2") (pin "14") (pinfunction "VDD_14") (pintype "power_in"))
      (node (ref "IC3") (pin "3") (pinfunction "VO_3") (pintype "passive"))
      (node (ref "ICSP") (pin "2") (pinfunction "2_2") (pintype "passive"))
      (node (ref "Q1") (pin "C") (pinfunction "C_C") (pintype "passive"))
      (node (ref "Q2") (pin "C") (pinfunction "C_C") (pintype "passive"))
      (node (ref "Q3") (pin "C") (pinfunction "C_C") (pintype "passive"))
      (node (ref "Q4") (pin "C") (pinfunction "C_C") (pintype "passive"))
      (node (ref "Q5") (pin "C") (pinfunction "C_C") (pintype "passive"))
      (node (ref "Q6") (pin "C") (pinfunction "C_C") (pintype "passive"))
      (node (ref "Q7") (pin "C") (pinfunction "C_C") (pintype "passive"))
      (node (ref "Q8") (pin "C") (pinfunction "C_C") (pintype "passive"))
      (node (ref "R9") (pin "2") (pinfunction "2_2") (pintype "passive"))
    )
    (net (code "49") (name "unconnected-(IC2-RA0{slash}AN0-Pad17)") (class "Default")
      (node (ref "IC2") (pin "17") (pinfunction "RA0/AN0_17") (pintype "bidirectional"))
    )
    (net (code "50") (name "unconnected-(IC2-RA1{slash}AN1-Pad18)") (class "Default")
      (node (ref "IC2") (pin "18") (pinfunction "RA1/AN1_18") (pintype "bidirectional"))
    )
    (net (code "51") (name "unconnected-(IC2-RA4{slash}TOCKI{slash}CMP2-Pad3)") (class "Default")
      (node (ref "IC2") (pin "3") (pinfunction "RA4/TOCKI/CMP2_3") (pintype "bidirectional"))
    )
    (net (code "52") (name "unconnected-(IC2-RA6{slash}OSC2{slash}CLKOUT-Pad15)") (class "Default")
      (node (ref "IC2") (pin "15") (pinfunction "RA6/OSC2/CLKOUT_15") (pintype "bidirectional"))
    )
    (net (code "53") (name "unconnected-(IC2-RA7{slash}OSC1{slash}CLKIN-Pad16)") (class "Default")
      (node (ref "IC2") (pin "16") (pinfunction "RA7/OSC1/CLKIN_16") (pintype "bidirectional"))
    )
  )
)
